# RotSense.net
KiCad netlist of a schematic drawn in Altium Designer
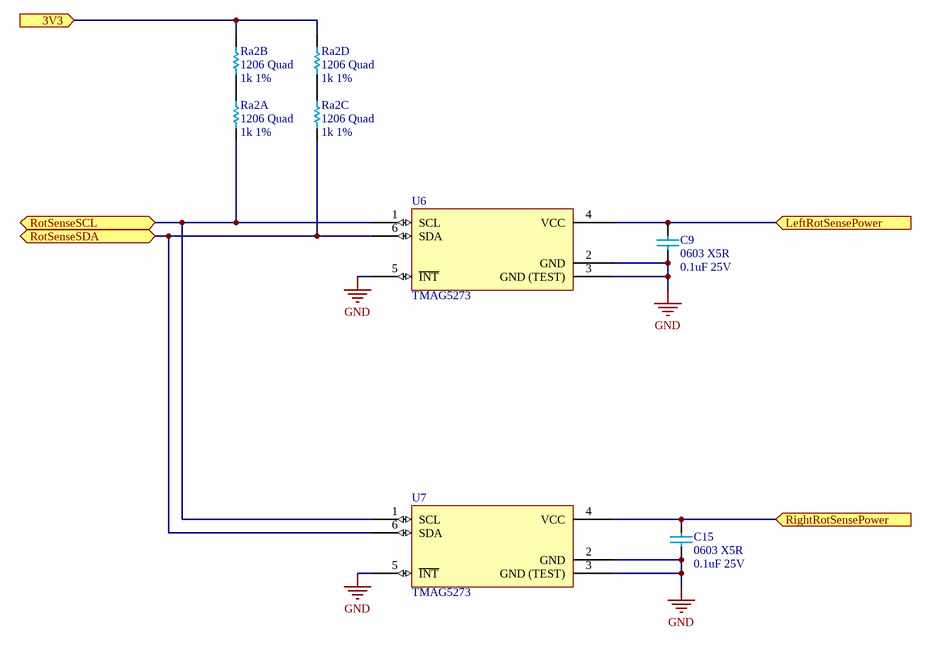
[diagram p0: RotSense.SchDoc]

(export (version "E")
  (design (tool "Eeschema 10.0.6"))
  (components
    (comp (ref "C9")
      (value "0603 X5R")
      (footprint "0603 capacitor - CAPC1608X06N")
      (description "0603, X5R or better")
      (fields (field (name "ALTIUM_VALUE") "0.1uF 25V"))
      (libsource (lib "Chip_Passives") (part "Cap 0.1uF 25V"))
    )
    (comp (ref "C15")
      (value "0603 X5R")
      (footprint "0603 capacitor - CAPC1608X06N")
      (description "0603, X5R or better")
      (fields (field (name "ALTIUM_VALUE") "0.1uF 25V"))
      (libsource (lib "Chip_Passives") (part "Cap 0.1uF 25V"))
    )
    (comp (ref "Ra2")
      (value "1206 Quad")
      (footprint "4x 1k 1% - CAC-80P320X160-8M")
      (description "Chip resistor")
      (fields (field (name "ALTIUM_VALUE") "1k 1%"))
      (libsource (lib "Chip_Passives") (part "Quad Res 1k 1% 1206"))
    )
    (comp (ref "U6")
      (value "TMAG5273")
      (footprint "TMAG5273 - SOT95P280X145-6M")
      (description "Low-Power Linear 3D Hall-Effect Sensor With I2C Interface")
      (libsource (lib "Sensors") (part "TMAG5273"))
    )
    (comp (ref "U7")
      (value "TMAG5273")
      (footprint "TMAG5273 - SOT95P280X145-6M")
      (description "Low-Power Linear 3D Hall-Effect Sensor With I2C Interface")
      (libsource (lib "Sensors") (part "TMAG5273"))
    )
  )
  (nets
    (net (code "1") (name "/3V3") (class "Default")
      (node (ref "Ra2") (pin "5") (pinfunction "5_5") (pintype "passive"))
      (node (ref "Ra2") (pin "7") (pinfunction "7_7") (pintype "passive"))
    )
    (net (code "2") (name "/LeftRotSensePower") (class "Default")
      (node (ref "C9") (pin "2") (pinfunction "2_2") (pintype "passive"))
      (node (ref "U6") (pin "4") (pinfunction "VCC_4") (pintype "passive"))
    )
    (net (code "3") (name "/RightRotSensePower") (class "Default")
      (node (ref "C15") (pin "2") (pinfunction "2_2") (pintype "passive"))
      (node (ref "U7") (pin "4") (pinfunction "VCC_4") (pintype "passive"))
    )
    (net (code "4") (name "/RotSenseSCL") (class "Default")
      (node (ref "Ra2") (pin "1") (pinfunction "1_1") (pintype "passive"))
      (node (ref "U6") (pin "1") (pinfunction "SCL_1") (pintype "bidirectional"))
      (node (ref "U7") (pin "1") (pinfunction "SCL_1") (pintype "bidirectional"))
    )
    (net (code "5") (name "/RotSenseSDA") (class "Default")
      (node (ref "Ra2") (pin "3") (pinfunction "3_3") (pintype "passive"))
      (node (ref "U6") (pin "6") (pinfunction "SDA_6") (pintype "bidirectional"))
      (node (ref "U7") (pin "6") (pinfunction "SDA_6") (pintype "bidirectional"))
    )
    (net (code "6") (name "GND") (class "Default")
      (node (ref "C15") (pin "1") (pinfunction "1_1") (pintype "passive"))
      (node (ref "C9") (pin "1") (pinfunction "1_1") (pintype "passive"))
      (node (ref "U6") (pin "2") (pinfunction "GND_2") (pintype "passive"))
      (node (ref "U6") (pin "3") (pinfunction "GND_(TEST)_3") (pintype "passive"))
      (node (ref "U6") (pin "5") (pinfunction "~{INT}_5") (pintype "bidirectional"))
      (node (ref "U7") (pin "2") (pinfunction "GND_2") (pintype "passive"))
      (node (ref "U7") (pin "3") (pinfunction "GND_(TEST)_3") (pintype "passive"))
      (node (ref "U7") (pin "5") (pinfunction "~{INT}_5") (pintype "bidirectional"))
    )
    (net (code "7") (name "Net-(Ra2-Pad2)") (class "Default")
      (node (ref "Ra2") (pin "2") (pinfunction "2_2") (pintype "passive"))
      (node (ref "Ra2") (pin "8") (pinfunction "8_8") (pintype "passive"))
    )
    (net (code "8") (name "Net-(Ra2-Pad4)") (class "Default")
      (node (ref "Ra2") (pin "4") (pinfunction "4_4") (pintype "passive"))
      (node (ref "Ra2") (pin "6") (pinfunction "6_6") (pintype "passive"))
    )
  )
)
